# Hormiga_877_FTDI_Rev_C.net
KiCad netlist of a schematic drawn in EAGLE
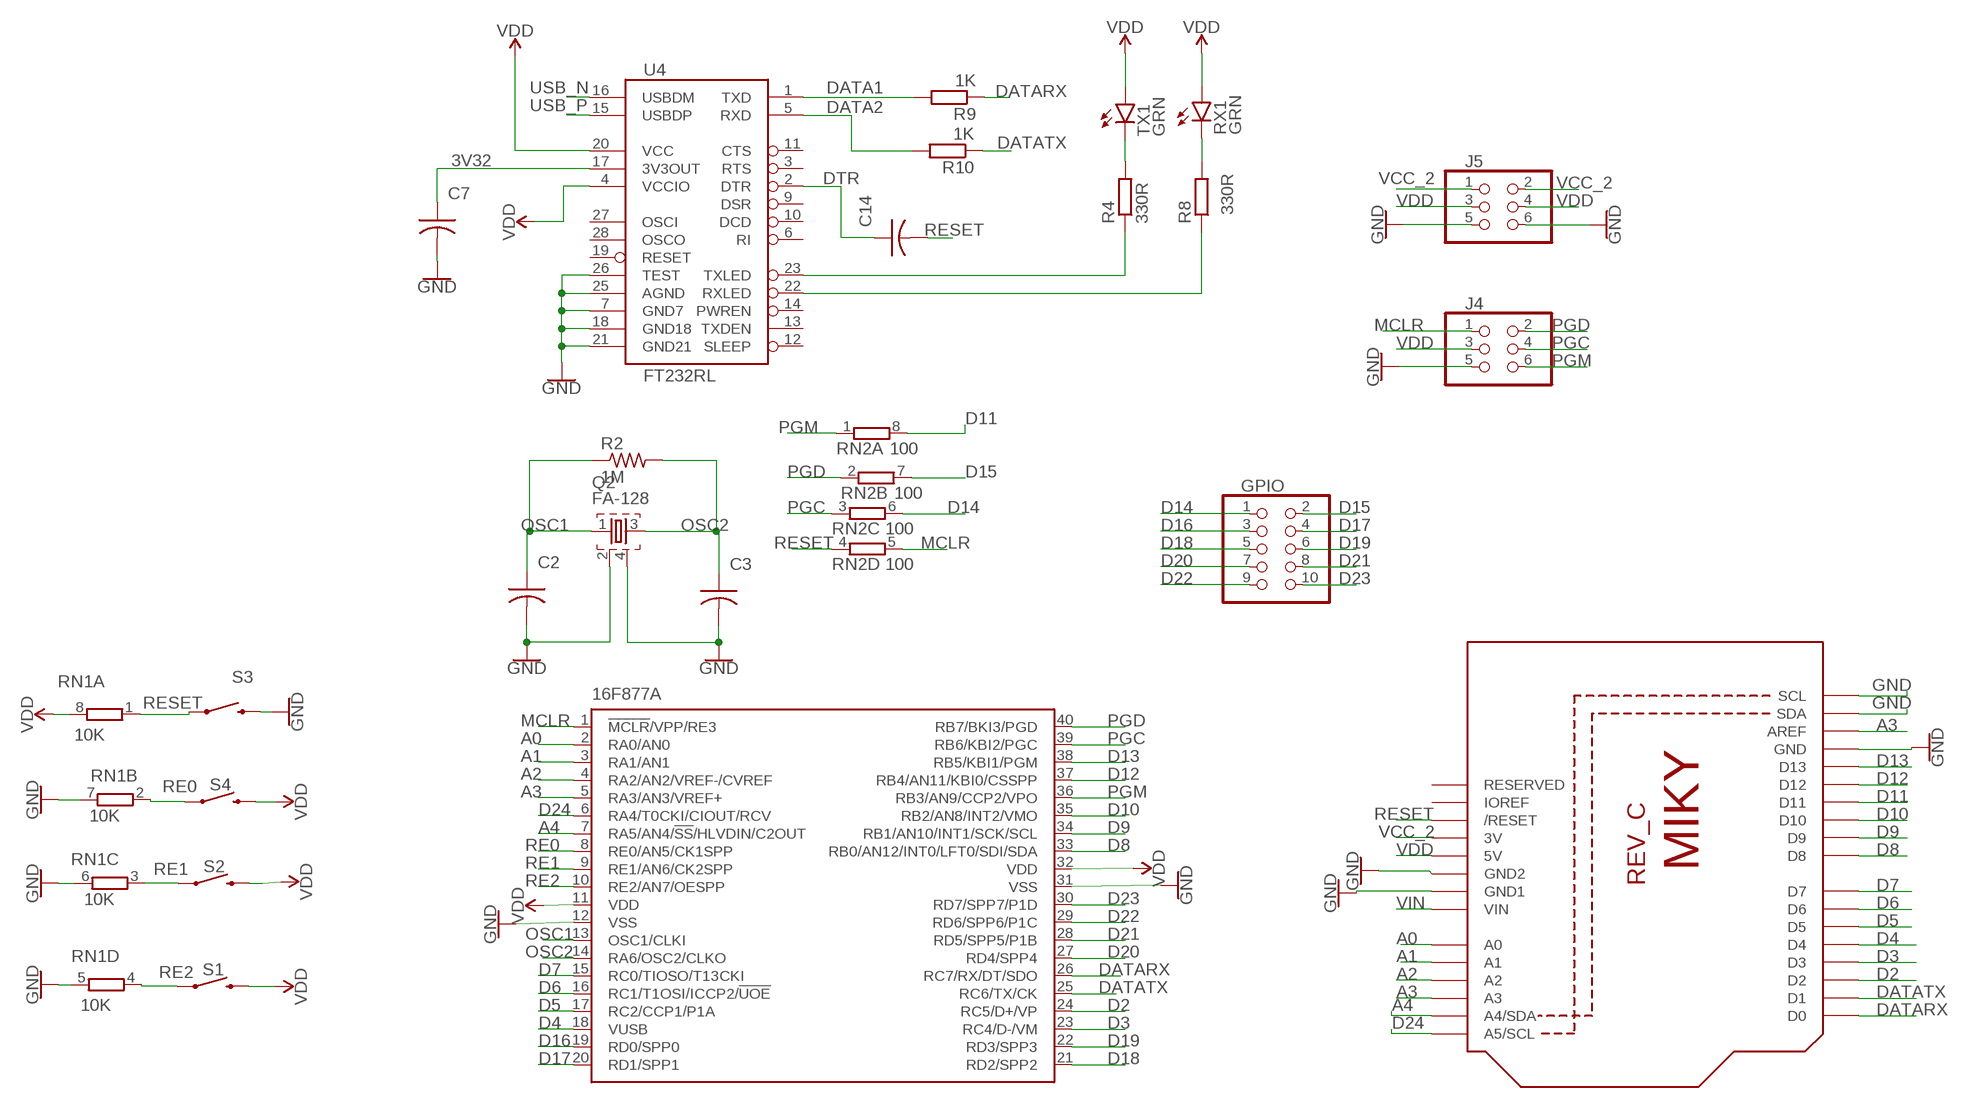
[diagram p0: schematic, sheet 1]
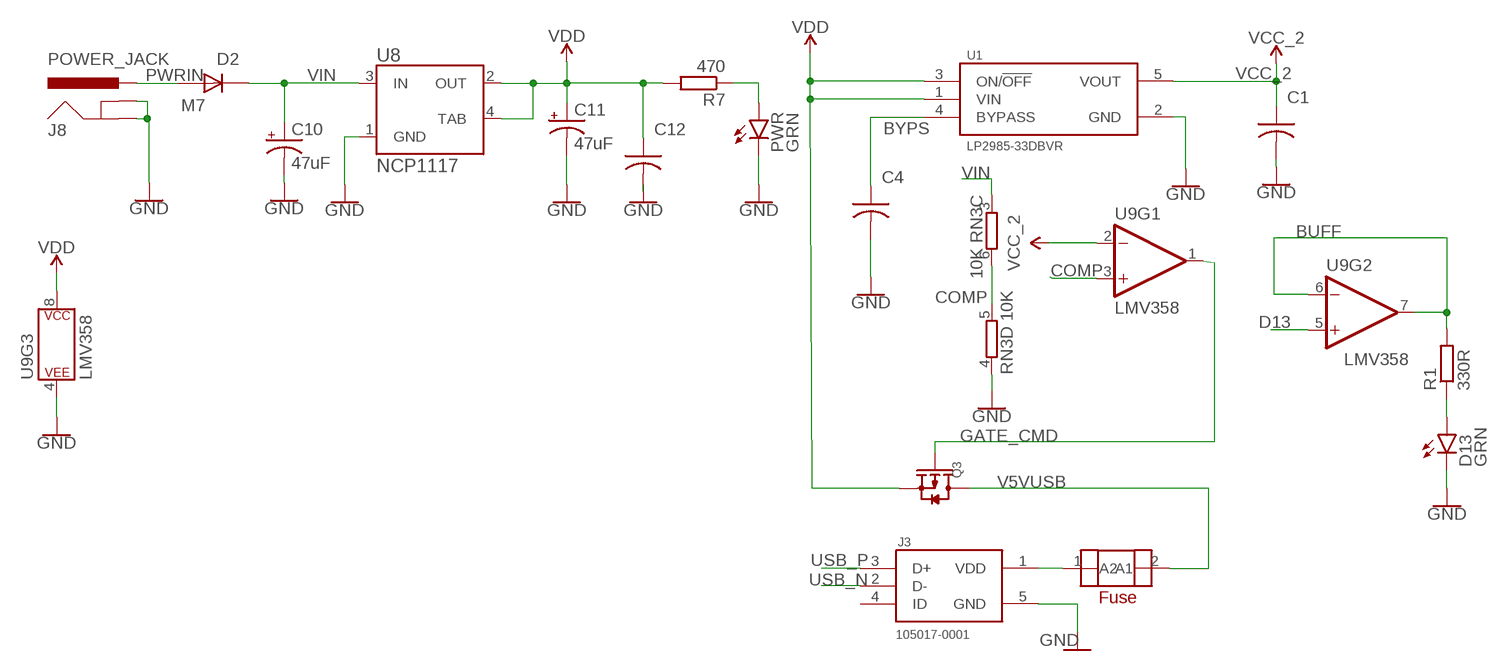
[diagram p1: schematic, sheet 2]

(export (version "E")
  (design (tool "Eeschema 10.0.6"))
  (components
    (comp (ref "16F877A")
      (value "PIC18F4550_40")
      (footprint "eagle-import:DIL40")
      (fields (field (name "MF") "MICROCHIP") (field (name "MPN") "PIC18F4550-I/P"))
      (libsource (lib "eagle-import") (part "PIC18F4_40550"))
    )
    (comp (ref "C2")
      (value "15pF")
      (footprint "eagle-import:C0603")
      (fields (field (name "MF") "FARNELL") (field (name "MPN") "CC0402JRNPO9BN150"))
      (libsource (lib "eagle-import") (part "C-USC0603"))
    )
    (comp (ref "C3")
      (value "15pF")
      (footprint "eagle-import:C0603")
      (fields (field (name "MF") "FARNELL") (field (name "MPN") "CC0402JRNPO9BN150"))
      (libsource (lib "eagle-import") (part "C-USC0603"))
    )
    (comp (ref "C7")
      (value "0.1uF")
      (footprint "eagle-import:C0603")
      (fields (field (name "MPN") "C0603C103J1RACTU"))
      (libsource (lib "eagle-import") (part "C-USC0603"))
    )
    (comp (ref "C14")
      (value "0.1uF")
      (footprint "eagle-import:C0603")
      (fields (field (name "MPN") "C0603C103J1RACTU"))
      (libsource (lib "eagle-import") (part "C-USC0603"))
    )
    (comp (ref "GPIO")
      (value "PINHD-2X5")
      (footprint "eagle-import:2X05")
      (libsource (lib "eagle-import") (part "PINHD-2X5"))
    )
    (comp (ref "J4")
      (value "ICSP")
      (footprint "eagle-import:2X03")
      (libsource (lib "eagle-import") (part "PINHD-2X3"))
    )
    (comp (ref "J5")
      (value "POWER")
      (footprint "eagle-import:2X03")
      (libsource (lib "eagle-import") (part "PINHD-2X3"))
    )
    (comp (ref "Q2")
      (value "FA-128")
      (footprint "eagle-import:FA-128")
      (libsource (lib "eagle-import") (part "FA-128"))
    )
    (comp (ref "R2")
      (value "1M")
      (footprint "eagle-import:R0603")
      (libsource (lib "eagle-import") (part "R-US_R0603"))
    )
    (comp (ref "R4")
      (value "330R")
      (footprint "eagle-import:R0805")
      (fields (field (name "MPN") "ERJ-6GEYJ331V"))
      (libsource (lib "eagle-import") (part "R-EU_R0805"))
    )
    (comp (ref "R8")
      (value "330R")
      (footprint "eagle-import:R0805")
      (fields (field (name "MPN") "ERJ-6GEYJ331V"))
      (libsource (lib "eagle-import") (part "R-EU_R0805"))
    )
    (comp (ref "R9")
      (value "1K")
      (footprint "eagle-import:R0805")
      (fields (field (name "MPN") "EXB-V8V103JV"))
      (libsource (lib "eagle-import") (part "R-EU_R0805"))
    )
    (comp (ref "R10")
      (value "1K")
      (footprint "eagle-import:R0805")
      (fields (field (name "MPN") "EXB-V8V103JV"))
      (libsource (lib "eagle-import") (part "R-EU_R0805"))
    )
    (comp (ref "RN1")
      (value "10K")
      (footprint "eagle-import:0603-ARC")
      (fields (field (name "MPN") "EXB-V8V103JV") (field (name "OC_NEWARK") "65T8998"))
      (libsource (lib "eagle-import") (part "4R-N0603-ARC"))
    )
    (comp (ref "RN2")
      (value "100")
      (footprint "eagle-import:0603-ARC")
      (libsource (lib "eagle-import") (part "4R-N0603-ARC"))
    )
    (comp (ref "RX1")
      (value "GRN")
      (footprint "eagle-import:CHIP-LED0603")
      (fields (field (name "MPN") "HSME-C191"))
      (libsource (lib "eagle-import") (part "LEDCHIP-LED0603"))
    )
    (comp (ref "S1")
      (value "MOMENTARY-SWITCH-SPST-SMD-5.2-REDUNDANT")
      (footprint "eagle-import:TACTILE_SWITCH_SMD_5.2MM")
      (fields (field (name "MPN") "TL3301AF160QG"))
      (libsource (lib "eagle-import") (part "MOMENTARY-SWITCH-SPST-SMD-5.2-REDUNDANT"))
    )
    (comp (ref "S2")
      (value "MOMENTARY-SWITCH-SPST-SMD-5.2-REDUNDANT")
      (footprint "eagle-import:TACTILE_SWITCH_SMD_5.2MM")
      (fields (field (name "MPN") "TL3301AF160QG"))
      (libsource (lib "eagle-import") (part "MOMENTARY-SWITCH-SPST-SMD-5.2-REDUNDANT"))
    )
    (comp (ref "S3")
      (value "MOMENTARY-SWITCH-SPST-SMD-5.2-REDUNDANT")
      (footprint "eagle-import:TACTILE_SWITCH_SMD_5.2MM")
      (fields (field (name "MPN") "TL3301AF160QG"))
      (libsource (lib "eagle-import") (part "MOMENTARY-SWITCH-SPST-SMD-5.2-REDUNDANT"))
    )
    (comp (ref "S4")
      (value "MOMENTARY-SWITCH-SPST-SMD-5.2-REDUNDANT")
      (footprint "eagle-import:TACTILE_SWITCH_SMD_5.2MM")
      (fields (field (name "MPN") "TL3301AF160QG"))
      (libsource (lib "eagle-import") (part "MOMENTARY-SWITCH-SPST-SMD-5.2-REDUNDANT"))
    )
    (comp (ref "TX1")
      (value "GRN")
      (footprint "eagle-import:CHIP-LED0603")
      (fields (field (name "MPN") "HSME-C191"))
      (libsource (lib "eagle-import") (part "LEDCHIP-LED0603"))
    )
    (comp (ref "U2")
      (value "ARDUINOR3-DIMENSION")
      (footprint "eagle-import:ARDUINOR3")
      (libsource (lib "eagle-import") (part "ARDUINOR3-DIMENSION"))
    )
    (comp (ref "U4")
      (value "FT232RL")
      (footprint "eagle-import:SSOP28DB")
      (fields (field (name "MPN") "FT232RL-REEL"))
      (libsource (lib "eagle-import") (part "FT232RLSSOP"))
    )
    (comp (ref "C1")
      (value "1.0uF")
      (footprint "eagle-import:C0603")
      (fields (field (name "MPN") "C1608X5R1E105K080AC"))
      (libsource (lib "eagle-import") (part "C-USC0603"))
    )
    (comp (ref "C4")
      (value "10nF")
      (footprint "eagle-import:C0603")
      (fields (field (name "MPN") "C0603C103K1RACTU"))
      (libsource (lib "eagle-import") (part "C-USC0603"))
    )
    (comp (ref "C10")
      (value "47uF")
      (footprint "eagle-import:PANASONIC_D")
      (fields (field (name "MPN") "EEE-1CA470WR"))
      (libsource (lib "eagle-import") (part "47UF-POLAR-PANASONIC_D-35V-20%"))
    )
    (comp (ref "C11")
      (value "47uF")
      (footprint "eagle-import:PANASONIC_D")
      (fields (field (name "MPN") "EEE-1CA470WR"))
      (libsource (lib "eagle-import") (part "47UF-POLAR-PANASONIC_D-35V-20%"))
    )
    (comp (ref "C12")
      (value "0.1uF")
      (footprint "eagle-import:C0603")
      (fields (field (name "MPN") "C0603C103J1RACTU"))
      (libsource (lib "eagle-import") (part "C-USC0603"))
    )
    (comp (ref "D2")
      (value "M7")
      (footprint "eagle-import:DIOM505270X240")
      (fields (field (name "MF") "Diodes Inc.") (field (name "MPN") "RFN1LAM7STFTR"))
      (libsource (lib "eagle-import") (part "M7"))
    )
    (comp (ref "D13")
      (value "GRN")
      (footprint "eagle-import:CHIP-LED0603")
      (fields (field (name "MPN") "HSME-C191"))
      (libsource (lib "eagle-import") (part "LEDCHIP-LED0603"))
    )
    (comp (ref "FUSE")
      (value "FUSE0603")
      (footprint "eagle-import:R0603")
      (libsource (lib "eagle-import") (part "FUSE0603"))
    )
    (comp (ref "J3")
      (value "105017-0001")
      (footprint "eagle-import:MOLEX_105017-0001")
      (fields (field (name "MF") "Molex"))
      (libsource (lib "eagle-import") (part "105017-0001"))
    )
    (comp (ref "J8")
      (value "POWER_JACK")
      (footprint "eagle-import:POWER_JACK_PTH")
      (fields (field (name "MPN") "FC681465P"))
      (libsource (lib "eagle-import") (part "POWER_JACK"))
    )
    (comp (ref "PWR")
      (value "GRN")
      (footprint "eagle-import:CHIP-LED0603")
      (fields (field (name "MPN") "HSME-C191"))
      (libsource (lib "eagle-import") (part "LEDCHIP-LED0603"))
    )
    (comp (ref "Q3")
      (value "SMD-MOSFET-P-CH-20V-2A(SOT-23)")
      (footprint "eagle-import:SOT-23")
      (fields
        (field (name "MF") "ON Semiconductor")
        (field (name "MP") "FDN340P")
        (field (name "MF_1") "FAIRCHILD SEMICONDUCTOR")
      )
      (libsource (lib "eagle-import") (part "SMD-MOSFET-P-CH-20V-2A(SOT-23)"))
    )
    (comp (ref "R1")
      (value "330R")
      (footprint "eagle-import:R0805")
      (fields (field (name "MPN") "ERJ-6GEYJ331V"))
      (libsource (lib "eagle-import") (part "R-EU_R0805"))
    )
    (comp (ref "R7")
      (value "470")
      (footprint "eagle-import:R0805")
      (fields (field (name "MPN") "ERJ-6GEYJ471V"))
      (libsource (lib "eagle-import") (part "R-EU_R0805"))
    )
    (comp (ref "RN3")
      (value "10K")
      (footprint "eagle-import:0603-ARC")
      (fields (field (name "MPN") "EXB-V8V103JV") (field (name "OC_NEWARK") "65T8998"))
      (libsource (lib "eagle-import") (part "4R-N0603-ARC"))
    )
    (comp (ref "U1")
      (value "LP2985-33DBVR")
      (footprint "eagle-import:SOT95P280X145-5N")
      (fields (field (name "MF") "Texas Instruments") (field (name "MF_1") "TEXAS INSTRUMENTS"))
      (libsource (lib "eagle-import") (part "LP2985-33DBVR"))
    )
    (comp (ref "U8")
      (value "NCP1117")
      (footprint "eagle-import:SOT223")
      (fields
        (field (name "MF") "ON Semiconductor")
        (field (name "MF_1") "ON SEMICONDUCTOR")
        (field (name "MPN") "NCP1117ST50T3G")
      )
      (libsource (lib "eagle-import") (part "NCP1117"))
    )
    (comp (ref "U9")
      (value "LMV358")
      (footprint "eagle-import:SO08")
      (fields
        (field (name "MF") "FAIRCHILD SEMICONDUCTOR")
        (field (name "MPN") "LMV358AM8X")
        (field (name "OC_NEWARK") "29H0537")
      )
      (libsource (lib "eagle-import") (part "LMV358SOIC"))
    )
  )
  (nets
    (net (code "1") (name "3V32") (class "Default")
      (node (ref "C7") (pin "1") (pinfunction "1_1") (pintype "passive"))
      (node (ref "U4") (pin "17") (pinfunction "3V3OUT_17") (pintype "output"))
    )
    (net (code "2") (name "A0") (class "Default")
      (node (ref "16F877A") (pin "2") (pinfunction "RA0/AN0_2") (pintype "bidirectional"))
      (node (ref "U2") (pin "A0") (pinfunction "A0_A0") (pintype "bidirectional"))
    )
    (net (code "3") (name "A1") (class "Default")
      (node (ref "16F877A") (pin "3") (pinfunction "RA1/AN1_3") (pintype "bidirectional"))
      (node (ref "U2") (pin "A1") (pinfunction "A1_A1") (pintype "bidirectional"))
    )
    (net (code "4") (name "A2") (class "Default")
      (node (ref "16F877A") (pin "4") (pinfunction "RA2/AN2/VREF-/CVREF_4") (pintype "bidirectional"))
      (node (ref "U2") (pin "A2") (pinfunction "A2_A2") (pintype "bidirectional"))
    )
    (net (code "5") (name "A3") (class "Default")
      (node (ref "16F877A") (pin "5") (pinfunction "RA3/AN3/VREF+_5") (pintype "bidirectional"))
      (node (ref "U2") (pin "A3") (pinfunction "A3_A3") (pintype "bidirectional"))
      (node (ref "U2") (pin "AREF") (pinfunction "AREF_AREF") (pintype "bidirectional"))
    )
    (net (code "6") (name "A4") (class "Default")
      (node (ref "16F877A") (pin "7") (pinfunction "RA5/AN4/~{SS}/HLVDIN/C2OUT_7") (pintype "bidirectional"))
      (node (ref "U2") (pin "A4") (pinfunction "A4/SDA_A4") (pintype "bidirectional"))
    )
    (net (code "7") (name "BUFF") (class "Default")
      (node (ref "R1") (pin "2") (pinfunction "2_2") (pintype "passive"))
      (node (ref "U9") (pin "6") (pinfunction "-IN_6") (pintype "input"))
      (node (ref "U9") (pin "7") (pinfunction "OUT_7") (pintype "output"))
    )
    (net (code "8") (name "BYPS") (class "Default")
      (node (ref "C4") (pin "1") (pinfunction "1_1") (pintype "passive"))
      (node (ref "U1") (pin "4") (pinfunction "BYPASS_4") (pintype "bidirectional"))
    )
    (net (code "9") (name "COMP") (class "Default")
      (node (ref "RN3") (pin "5") (pinfunction "2_5") (pintype "passive"))
      (node (ref "RN3") (pin "6") (pinfunction "2_6") (pintype "passive"))
      (node (ref "U9") (pin "3") (pinfunction "+IN_3") (pintype "input"))
    )
    (net (code "10") (name "D2") (class "Default")
      (node (ref "16F877A") (pin "24") (pinfunction "RC5/D+/VP_24") (pintype "bidirectional"))
      (node (ref "U2") (pin "D2") (pinfunction "D2_D2") (pintype "bidirectional"))
    )
    (net (code "11") (name "D3") (class "Default")
      (node (ref "16F877A") (pin "23") (pinfunction "RC4/D-/VM_23") (pintype "bidirectional"))
      (node (ref "U2") (pin "D3") (pinfunction "D3_D3") (pintype "bidirectional"))
    )
    (net (code "12") (name "D4") (class "Default")
      (node (ref "16F877A") (pin "18") (pinfunction "VUSB_18") (pintype "bidirectional"))
      (node (ref "U2") (pin "D4") (pinfunction "D4_D4") (pintype "bidirectional"))
    )
    (net (code "13") (name "D5") (class "Default")
      (node (ref "16F877A") (pin "17") (pinfunction "RC2/CCP1/P1A_17") (pintype "bidirectional"))
      (node (ref "U2") (pin "D5") (pinfunction "D5_D5") (pintype "bidirectional"))
    )
    (net (code "14") (name "D6") (class "Default")
      (node (ref "16F877A") (pin "16") (pinfunction "RC1/T1OSI/ICCP2/~{UOE}_16") (pintype "bidirectional"))
      (node (ref "U2") (pin "D6") (pinfunction "D6_D6") (pintype "bidirectional"))
    )
    (net (code "15") (name "D7") (class "Default")
      (node (ref "16F877A") (pin "15") (pinfunction "RC0/TIOSO/T13CKI_15") (pintype "bidirectional"))
      (node (ref "U2") (pin "D7") (pinfunction "D7_D7") (pintype "bidirectional"))
    )
    (net (code "16") (name "D8") (class "Default")
      (node (ref "16F877A") (pin "33") (pinfunction "RB0/AN12/INT0/LFT0/SDI/SDA_33") (pintype "bidirectional"))
      (node (ref "U2") (pin "D8") (pinfunction "D8_D8") (pintype "bidirectional"))
    )
    (net (code "17") (name "D9") (class "Default")
      (node (ref "16F877A") (pin "34") (pinfunction "RB1/AN10/INT1/SCK/SCL_34") (pintype "bidirectional"))
      (node (ref "U2") (pin "D9") (pinfunction "D9_D9") (pintype "bidirectional"))
    )
    (net (code "18") (name "D10") (class "Default")
      (node (ref "16F877A") (pin "35") (pinfunction "RB2/AN8/INT2/VMO_35") (pintype "bidirectional"))
      (node (ref "U2") (pin "D10") (pinfunction "D10_D10") (pintype "bidirectional"))
    )
    (net (code "19") (name "D11") (class "Default")
      (node (ref "RN2") (pin "8") (pinfunction "2_8") (pintype "passive"))
      (node (ref "U2") (pin "D11") (pinfunction "D11_D11") (pintype "bidirectional"))
    )
    (net (code "20") (name "D12") (class "Default")
      (node (ref "16F877A") (pin "37") (pinfunction "RB4/AN11/KBI0/CSSPP_37") (pintype "bidirectional"))
      (node (ref "U2") (pin "D12") (pinfunction "D12_D12") (pintype "bidirectional"))
    )
    (net (code "21") (name "D13") (class "Default")
      (node (ref "16F877A") (pin "38") (pinfunction "RB5/KBI1/PGM_38") (pintype "bidirectional"))
      (node (ref "U2") (pin "D13") (pinfunction "D13_D13") (pintype "bidirectional"))
      (node (ref "U9") (pin "5") (pinfunction "+IN_5") (pintype "input"))
    )
    (net (code "22") (name "D14") (class "Default")
      (node (ref "GPIO") (pin "1") (pinfunction "1_1") (pintype "passive"))
      (node (ref "RN2") (pin "6") (pinfunction "2_6") (pintype "passive"))
    )
    (net (code "23") (name "D15") (class "Default")
      (node (ref "GPIO") (pin "2") (pinfunction "2_2") (pintype "passive"))
      (node (ref "RN2") (pin "7") (pinfunction "2_7") (pintype "passive"))
    )
    (net (code "24") (name "D16") (class "Default")
      (node (ref "16F877A") (pin "19") (pinfunction "RD0/SPP0_19") (pintype "bidirectional"))
      (node (ref "GPIO") (pin "3") (pinfunction "3_3") (pintype "passive"))
    )
    (net (code "25") (name "D17") (class "Default")
      (node (ref "16F877A") (pin "20") (pinfunction "RD1/SPP1_20") (pintype "bidirectional"))
      (node (ref "GPIO") (pin "4") (pinfunction "4_4") (pintype "passive"))
    )
    (net (code "26") (name "D18") (class "Default")
      (node (ref "16F877A") (pin "21") (pinfunction "RD2/SPP2_21") (pintype "bidirectional"))
      (node (ref "GPIO") (pin "5") (pinfunction "5_5") (pintype "passive"))
    )
    (net (code "27") (name "D19") (class "Default")
      (node (ref "16F877A") (pin "22") (pinfunction "RD3/SPP3_22") (pintype "bidirectional"))
      (node (ref "GPIO") (pin "6") (pinfunction "6_6") (pintype "passive"))
    )
    (net (code "28") (name "D20") (class "Default")
      (node (ref "16F877A") (pin "27") (pinfunction "RD4/SPP4_27") (pintype "bidirectional"))
      (node (ref "GPIO") (pin "7") (pinfunction "7_7") (pintype "passive"))
    )
    (net (code "29") (name "D21") (class "Default")
      (node (ref "16F877A") (pin "28") (pinfunction "RD5/SPP5/P1B_28") (pintype "bidirectional"))
      (node (ref "GPIO") (pin "8") (pinfunction "8_8") (pintype "passive"))
    )
    (net (code "30") (name "D22") (class "Default")
      (node (ref "16F877A") (pin "29") (pinfunction "RD6/SPP6/P1C_29") (pintype "bidirectional"))
      (node (ref "GPIO") (pin "9") (pinfunction "9_9") (pintype "passive"))
    )
    (net (code "31") (name "D23") (class "Default")
      (node (ref "16F877A") (pin "30") (pinfunction "RD7/SPP7/P1D_30") (pintype "bidirectional"))
      (node (ref "GPIO") (pin "10") (pinfunction "10_10") (pintype "passive"))
    )
    (net (code "32") (name "D24") (class "Default")
      (node (ref "16F877A") (pin "6") (pinfunction "RA4/T0CKI/CIOUT/RCV_6") (pintype "bidirectional"))
      (node (ref "U2") (pin "A5") (pinfunction "A5/SCL_A5") (pintype "bidirectional"))
    )
    (net (code "33") (name "DATA1") (class "Default")
      (node (ref "R9") (pin "2") (pinfunction "2_2") (pintype "passive"))
      (node (ref "U4") (pin "1") (pinfunction "TXD_1") (pintype "output"))
    )
    (net (code "34") (name "DATA2") (class "Default")
      (node (ref "R10") (pin "2") (pinfunction "2_2") (pintype "passive"))
      (node (ref "U4") (pin "5") (pinfunction "RXD_5") (pintype "input"))
    )
    (net (code "35") (name "DATARX") (class "Default")
      (node (ref "16F877A") (pin "26") (pinfunction "RC7/RX/DT/SDO_26") (pintype "bidirectional"))
      (node (ref "R9") (pin "1") (pinfunction "1_1") (pintype "passive"))
      (node (ref "U2") (pin "D0") (pinfunction "D0_D0") (pintype "bidirectional"))
    )
    (net (code "36") (name "DATATX") (class "Default")
      (node (ref "16F877A") (pin "25") (pinfunction "RC6/TX/CK_25") (pintype "bidirectional"))
      (node (ref "R10") (pin "1") (pinfunction "1_1") (pintype "passive"))
      (node (ref "U2") (pin "D1") (pinfunction "D1_D1") (pintype "bidirectional"))
    )
    (net (code "37") (name "DTR") (class "Default")
      (node (ref "C14") (pin "1") (pinfunction "1_1") (pintype "passive"))
      (node (ref "U4") (pin "2") (pinfunction "DTR_2") (pintype "output"))
    )
    (net (code "38") (name "GATE_CMD") (class "Default")
      (node (ref "Q3") (pin "1") (pinfunction "G_1") (pintype "passive"))
      (node (ref "U9") (pin "1") (pinfunction "OUT_1") (pintype "output"))
    )
    (net (code "39") (name "GND") (class "Default")
      (node (ref "16F877A") (pin "12") (pinfunction "VSS_12") (pintype "power_in"))
      (node (ref "16F877A") (pin "31") (pinfunction "VSS_31") (pintype "power_in"))
      (node (ref "C1") (pin "2") (pinfunction "2_2") (pintype "passive"))
      (node (ref "C10") (pin "-") (pinfunction "-_-") (pintype "passive"))
      (node (ref "C11") (pin "-") (pinfunction "-_-") (pintype "passive"))
      (node (ref "C12") (pin "2") (pinfunction "2_2") (pintype "passive"))
      (node (ref "C2") (pin "2") (pinfunction "2_2") (pintype "passive"))
      (node (ref "C3") (pin "2") (pinfunction "2_2") (pintype "passive"))
      (node (ref "C4") (pin "2") (pinfunction "2_2") (pintype "passive"))
      (node (ref "C7") (pin "2") (pinfunction "2_2") (pintype "passive"))
      (node (ref "D13") (pin "C") (pinfunction "C_C") (pintype "passive"))
      (node (ref "J3") (pin "5") (pinfunction "GND_5") (pintype "power_in"))
      (node (ref "J4") (pin "5") (pinfunction "5_5") (pintype "passive"))
      (node (ref "J5") (pin "5") (pinfunction "5_5") (pintype "passive"))
      (node (ref "J5") (pin "6") (pinfunction "6_6") (pintype "passive"))
      (node (ref "J8") (pin "GND") (pinfunction "GND_GND") (pintype "bidirectional"))
      (node (ref "J8") (pin "GNDBREAK") (pinfunction "GNDBREAK_GNDBREAK") (pintype "bidirectional"))
      (node (ref "PWR") (pin "C") (pinfunction "C_C") (pintype "passive"))
      (node (ref "Q2") (pin "2") (pinfunction "2_2") (pintype "passive"))
      (node (ref "Q2") (pin "4") (pinfunction "4_4") (pintype "passive"))
      (node (ref "RN1") (pin "5") (pinfunction "2_5") (pintype "passive"))
      (node (ref "RN1") (pin "6") (pinfunction "2_6") (pintype "passive"))
      (node (ref "RN1") (pin "7") (pinfunction "2_7") (pintype "passive"))
      (node (ref "RN3") (pin "4") (pinfunction "1_4") (pintype "passive"))
      (node (ref "S3") (pin "3") (pinfunction "2_3") (pintype "passive"))
      (node (ref "S3") (pin "4") (pinfunction "2_4") (pintype "passive"))
      (node (ref "U1") (pin "2") (pinfunction "GND_2") (pintype "power_in"))
      (node (ref "U2") (pin "GND") (pinfunction "GND_GND") (pintype "power_in"))
      (node (ref "U2") (pin "GND1") (pinfunction "GND1_GND1") (pintype "power_in"))
      (node (ref "U2") (pin "GND2") (pinfunction "GND2_GND2") (pintype "power_in"))
      (node (ref "U2") (pin "SCL") (pinfunction "SCL_SCL") (pintype "bidirectional"))
      (node (ref "U2") (pin "SDA") (pinfunction "SDA_SDA") (pintype "bidirectional"))
      (node (ref "U4") (pin "18") (pinfunction "GND18_18") (pintype "power_in"))
      (node (ref "U4") (pin "21") (pinfunction "GND21_21") (pintype "power_in"))
      (node (ref "U4") (pin "25") (pinfunction "AGND_25") (pintype "power_in"))
      (node (ref "U4") (pin "26") (pinfunction "TEST_26") (pintype "input"))
      (node (ref "U4") (pin "7") (pinfunction "GND7_7") (pintype "power_in"))
      (node (ref "U8") (pin "1") (pinfunction "GND_1") (pintype "bidirectional"))
      (node (ref "U9") (pin "4") (pinfunction "P$V-_4") (pintype "bidirectional"))
    )
    (net (code "40") (name "MCLR") (class "Default")
      (node (ref "16F877A") (pin "1") (pinfunction "~{MCLR}/VPP/RE3_1") (pintype "input"))
      (node (ref "J4") (pin "1") (pinfunction "1_1") (pintype "passive"))
      (node (ref "RN2") (pin "5") (pinfunction "2_5") (pintype "passive"))
    )
    (net (code "41") (name "Net-(D13-PadA)") (class "Default")
      (node (ref "D13") (pin "A") (pinfunction "A_A") (pintype "passive"))
      (node (ref "R1") (pin "1") (pinfunction "1_1") (pintype "passive"))
    )
    (net (code "42") (name "Net-(FUSE-A1)") (class "Default")
      (node (ref "FUSE") (pin "1") (pinfunction "A1_1") (pintype "bidirectional"))
      (node (ref "J3") (pin "1") (pinfunction "VDD_1") (pintype "power_in"))
    )
    (net (code "43") (name "Net-(PWR-PadA)") (class "Default")
      (node (ref "PWR") (pin "A") (pinfunction "A_A") (pintype "passive"))
      (node (ref "R7") (pin "1") (pinfunction "1_1") (pintype "passive"))
    )
    (net (code "44") (name "Net-(R4-Pad2)") (class "Default")
      (node (ref "R4") (pin "2") (pinfunction "2_2") (pintype "passive"))
      (node (ref "TX1") (pin "C") (pinfunction "C_C") (pintype "passive"))
    )
    (net (code "45") (name "Net-(R8-Pad2)") (class "Default")
      (node (ref "R8") (pin "2") (pinfunction "2_2") (pintype "passive"))
      (node (ref "RX1") (pin "C") (pinfunction "C_C") (pintype "passive"))
    )
    (net (code "46") (name "Net-(U4-RXLED)") (class "Default")
      (node (ref "R8") (pin "1") (pinfunction "1_1") (pintype "passive"))
      (node (ref "U4") (pin "22") (pinfunction "RXLED_22") (pintype "input"))
    )
    (net (code "47") (name "Net-(U4-TXLED)") (class "Default")
      (node (ref "R4") (pin "1") (pinfunction "1_1") (pintype "passive"))
      (node (ref "U4") (pin "23") (pinfunction "TXLED_23") (pintype "input"))
    )
    (net (code "48") (name "OSC1") (class "Default")
      (node (ref "16F877A") (pin "13") (pinfunction "OSC1/CLKI_13") (pintype "input"))
      (node (ref "C2") (pin "1") (pinfunction "1_1") (pintype "passive"))
      (node (ref "Q2") (pin "1") (pinfunction "1_1") (pintype "passive"))
      (node (ref "R2") (pin "1") (pinfunction "1_1") (pintype "passive"))
    )
    (net (code "49") (name "OSC2") (class "Default")
      (node (ref "16F877A") (pin "14") (pinfunction "RA6/OSC2/CLKO_14") (pintype "output"))
      (node (ref "C3") (pin "1") (pinfunction "1_1") (pintype "passive"))
      (node (ref "Q2") (pin "3") (pinfunction "3_3") (pintype "passive"))
      (node (ref "R2") (pin "2") (pinfunction "2_2") (pintype "passive"))
    )
    (net (code "50") (name "PGC") (class "Default")
      (node (ref "16F877A") (pin "39") (pinfunction "RB6/KBI2/PGC_39") (pintype "bidirectional"))
      (node (ref "J4") (pin "4") (pinfunction "4_4") (pintype "passive"))
      (node (ref "RN2") (pin "3") (pinfunction "1_3") (pintype "passive"))
    )
    (net (code "51") (name "PGD") (class "Default")
      (node (ref "16F877A") (pin "40") (pinfunction "RB7/BKI3/PGD_40") (pintype "bidirectional"))
      (node (ref "J4") (pin "2") (pinfunction "2_2") (pintype "passive"))
      (node (ref "RN2") (pin "2") (pinfunction "1_2") (pintype "passive"))
    )
    (net (code "52") (name "PGM") (class "Default")
      (node (ref "16F877A") (pin "36") (pinfunction "RB3/AN9/CCP2/VPO_36") (pintype "bidirectional"))
      (node (ref "J4") (pin "6") (pinfunction "6_6") (pintype "passive"))
      (node (ref "RN2") (pin "1") (pinfunction "1_1") (pintype "passive"))
    )
    (net (code "53") (name "PWRIN") (class "Default")
      (node (ref "D2") (pin "A") (pinfunction "A_A") (pintype "passive"))
      (node (ref "J8") (pin "PWR") (pinfunction "PWR_PWR") (pintype "bidirectional"))
    )
    (net (code "54") (name "RE0") (class "Default")
      (node (ref "16F877A") (pin "8") (pinfunction "RE0/AN5/CK1SPP_8") (pintype "bidirectional"))
      (node (ref "RN1") (pin "2") (pinfunction "1_2") (pintype "passive"))
      (node (ref "S4") (pin "1") (pinfunction "1_1") (pintype "passive"))
      (node (ref "S4") (pin "2") (pinfunction "1_2") (pintype "passive"))
    )
    (net (code "55") (name "RE1") (class "Default")
      (node (ref "16F877A") (pin "9") (pinfunction "RE1/AN6/CK2SPP_9") (pintype "bidirectional"))
      (node (ref "RN1") (pin "3") (pinfunction "1_3") (pintype "passive"))
      (node (ref "S2") (pin "1") (pinfunction "1_1") (pintype "passive"))
      (node (ref "S2") (pin "2") (pinfunction "1_2") (pintype "passive"))
    )
    (net (code "56") (name "RE2") (class "Default")
      (node (ref "16F877A") (pin "10") (pinfunction "RE2/AN7/OESPP_10") (pintype "bidirectional"))
      (node (ref "RN1") (pin "4") (pinfunction "1_4") (pintype "passive"))
      (node (ref "S1") (pin "1") (pinfunction "1_1") (pintype "passive"))
      (node (ref "S1") (pin "2") (pinfunction "1_2") (pintype "passive"))
    )
    (net (code "57") (name "RESET") (class "Default")
      (node (ref "C14") (pin "2") (pinfunction "2_2") (pintype "passive"))
      (node (ref "RN1") (pin "1") (pinfunction "1_1") (pintype "passive"))
      (node (ref "RN2") (pin "4") (pinfunction "1_4") (pintype "passive"))
      (node (ref "S3") (pin "1") (pinfunction "1_1") (pintype "passive"))
      (node (ref "S3") (pin "2") (pinfunction "1_2") (pintype "passive"))
      (node (ref "U2") (pin "RESET") (pinfunction "/RESET_RESET") (pintype "bidirectional"))
    )
    (net (code "58") (name "USB_N") (class "Default")
      (node (ref "J3") (pin "2") (pinfunction "D-_2") (pintype "bidirectional"))
      (node (ref "U4") (pin "16") (pinfunction "USBDM_16") (pintype "bidirectional"))
    )
    (net (code "59") (name "USB_P") (class "Default")
      (node (ref "J3") (pin "3") (pinfunction "D+_3") (pintype "bidirectional"))
      (node (ref "U4") (pin "15") (pinfunction "USBDP_15") (pintype "bidirectional"))
    )
    (net (code "60") (name "V5VUSB") (class "Default")
      (node (ref "FUSE") (pin "2") (pinfunction "A2_2") (pintype "bidirectional"))
      (node (ref "Q3") (pin "3") (pinfunction "D_3") (pintype "passive"))
    )
    (net (code "61") (name "VCC_2") (class "Default")
      (node (ref "C1") (pin "1") (pinfunction "1_1") (pintype "passive"))
      (node (ref "J5") (pin "1") (pinfunction "1_1") (pintype "passive"))
      (node (ref "J5") (pin "2") (pinfunction "2_2") (pintype "passive"))
      (node (ref "U1") (pin "5") (pinfunction "VOUT_5") (pintype "output"))
      (node (ref "U2") (pin "3V") (pinfunction "3V_3V") (pintype "power_in"))
      (node (ref "U9") (pin "2") (pinfunction "-IN_2") (pintype "input"))
    )
    (net (code "62") (name "VDD") (class "Default")
      (node (ref "16F877A") (pin "11") (pinfunction "VDD_11") (pintype "power_in"))
      (node (ref "16F877A") (pin "32") (pinfunction "VDD_32") (pintype "power_in"))
      (node (ref "C11") (pin "+") (pinfunction "+_+") (pintype "passive"))
      (node (ref "C12") (pin "1") (pinfunction "1_1") (pintype "passive"))
      (node (ref "J4") (pin "3") (pinfunction "3_3") (pintype "passive"))
      (node (ref "J5") (pin "3") (pinfunction "3_3") (pintype "passive"))
      (node (ref "J5") (pin "4") (pinfunction "4_4") (pintype "passive"))
      (node (ref "Q3") (pin "2") (pinfunction "S_2") (pintype "passive"))
      (node (ref "R7") (pin "2") (pinfunction "2_2") (pintype "passive"))
      (node (ref "RN1") (pin "8") (pinfunction "2_8") (pintype "passive"))
      (node (ref "RX1") (pin "A") (pinfunction "A_A") (pintype "passive"))
      (node (ref "S1") (pin "3") (pinfunction "2_3") (pintype "passive"))
      (node (ref "S1") (pin "4") (pinfunction "2_4") (pintype "passive"))
      (node (ref "S2") (pin "3") (pinfunction "2_3") (pintype "passive"))
      (node (ref "S2") (pin "4") (pinfunction "2_4") (pintype "passive"))
      (node (ref "S4") (pin "3") (pinfunction "2_3") (pintype "passive"))
      (node (ref "S4") (pin "4") (pinfunction "2_4") (pintype "passive"))
      (node (ref "TX1") (pin "A") (pinfunction "A_A") (pintype "passive"))
      (node (ref "U1") (pin "1") (pinfunction "VIN_1") (pintype "input"))
      (node (ref "U1") (pin "3") (pinfunction "ON/~{OFF}_3") (pintype "input"))
      (node (ref "U2") (pin "5V") (pinfunction "5V_5V") (pintype "power_in"))
      (node (ref "U4") (pin "20") (pinfunction "VCC_20") (pintype "power_in"))
      (node (ref "U4") (pin "4") (pinfunction "VCCIO_4") (pintype "power_in"))
      (node (ref "U8") (pin "2") (pinfunction "OUT_2") (pintype "bidirectional"))
      (node (ref "U8") (pin "4") (pinfunction "TAB_4") (pintype "bidirectional"))
      (node (ref "U9") (pin "8") (pinfunction "P$V+_8") (pintype "bidirectional"))
    )
    (net (code "63") (name "VIN") (class "Default")
      (node (ref "C10") (pin "+") (pinfunction "+_+") (pintype "passive"))
      (node (ref "D2") (pin "C") (pinfunction "C_C") (pintype "passive"))
      (node (ref "RN3") (pin "3") (pinfunction "1_3") (pintype "passive"))
      (node (ref "U2") (pin "VIN") (pinfunction "VIN_VIN") (pintype "power_in"))
      (node (ref "U8") (pin "3") (pinfunction "IN_3") (pintype "bidirectional"))
    )
    (net (code "64") (name "unconnected-(J3-ID-Pad4)") (class "Default")
      (node (ref "J3") (pin "4") (pinfunction "ID_4") (pintype "passive"))
    )
    (net (code "65") (name "unconnected-(U2-PadIOREF)") (class "Default")
      (node (ref "U2") (pin "IOREF") (pinfunction "IOREF_IOREF") (pintype "output"))
    )
    (net (code "66") (name "unconnected-(U2-PadRESERVED)") (class "Default")
      (node (ref "U2") (pin "RESERVED") (pinfunction "RESERVED_RESERVED") (pintype "no_connect"))
    )
    (net (code "67") (name "unconnected-(U4-CTS-Pad11)") (class "Default")
      (node (ref "U4") (pin "11") (pinfunction "CTS_11") (pintype "input"))
    )
    (net (code "68") (name "unconnected-(U4-DCD-Pad10)") (class "Default")
      (node (ref "U4") (pin "10") (pinfunction "DCD_10") (pintype "input"))
    )
    (net (code "69") (name "unconnected-(U4-DSR-Pad9)") (class "Default")
      (node (ref "U4") (pin "9") (pinfunction "DSR_9") (pintype "input"))
    )
    (net (code "70") (name "unconnected-(U4-OSCI-Pad27)") (class "Default")
      (node (ref "U4") (pin "27") (pinfunction "OSCI_27") (pintype "input"))
    )
    (net (code "71") (name "unconnected-(U4-OSCO-Pad28)") (class "Default")
      (node (ref "U4") (pin "28") (pinfunction "OSCO_28") (pintype "output"))
    )
    (net (code "72") (name "unconnected-(U4-PWREN-Pad14)") (class "Default")
      (node (ref "U4") (pin "14") (pinfunction "PWREN_14") (pintype "input"))
    )
    (net (code "73") (name "unconnected-(U4-RESET-Pad19)") (class "Default")
      (node (ref "U4") (pin "19") (pinfunction "RESET_19") (pintype "input"))
    )
    (net (code "74") (name "unconnected-(U4-RI-Pad6)") (class "Default")
      (node (ref "U4") (pin "6") (pinfunction "RI_6") (pintype "input"))
    )
    (net (code "75") (name "unconnected-(U4-RTS-Pad3)") (class "Default")
      (node (ref "U4") (pin "3") (pinfunction "RTS_3") (pintype "output"))
    )
    (net (code "76") (name "unconnected-(U4-SLEEP-Pad12)") (class "Default")
      (node (ref "U4") (pin "12") (pinfunction "SLEEP_12") (pintype "input"))
    )
    (net (code "77") (name "unconnected-(U4-TXDEN-Pad13)") (class "Default")
      (node (ref "U4") (pin "13") (pinfunction "TXDEN_13") (pintype "input"))
    )
  )
)
